# arm-pro-mini.net
KiCad netlist of a schematic drawn in EAGLE
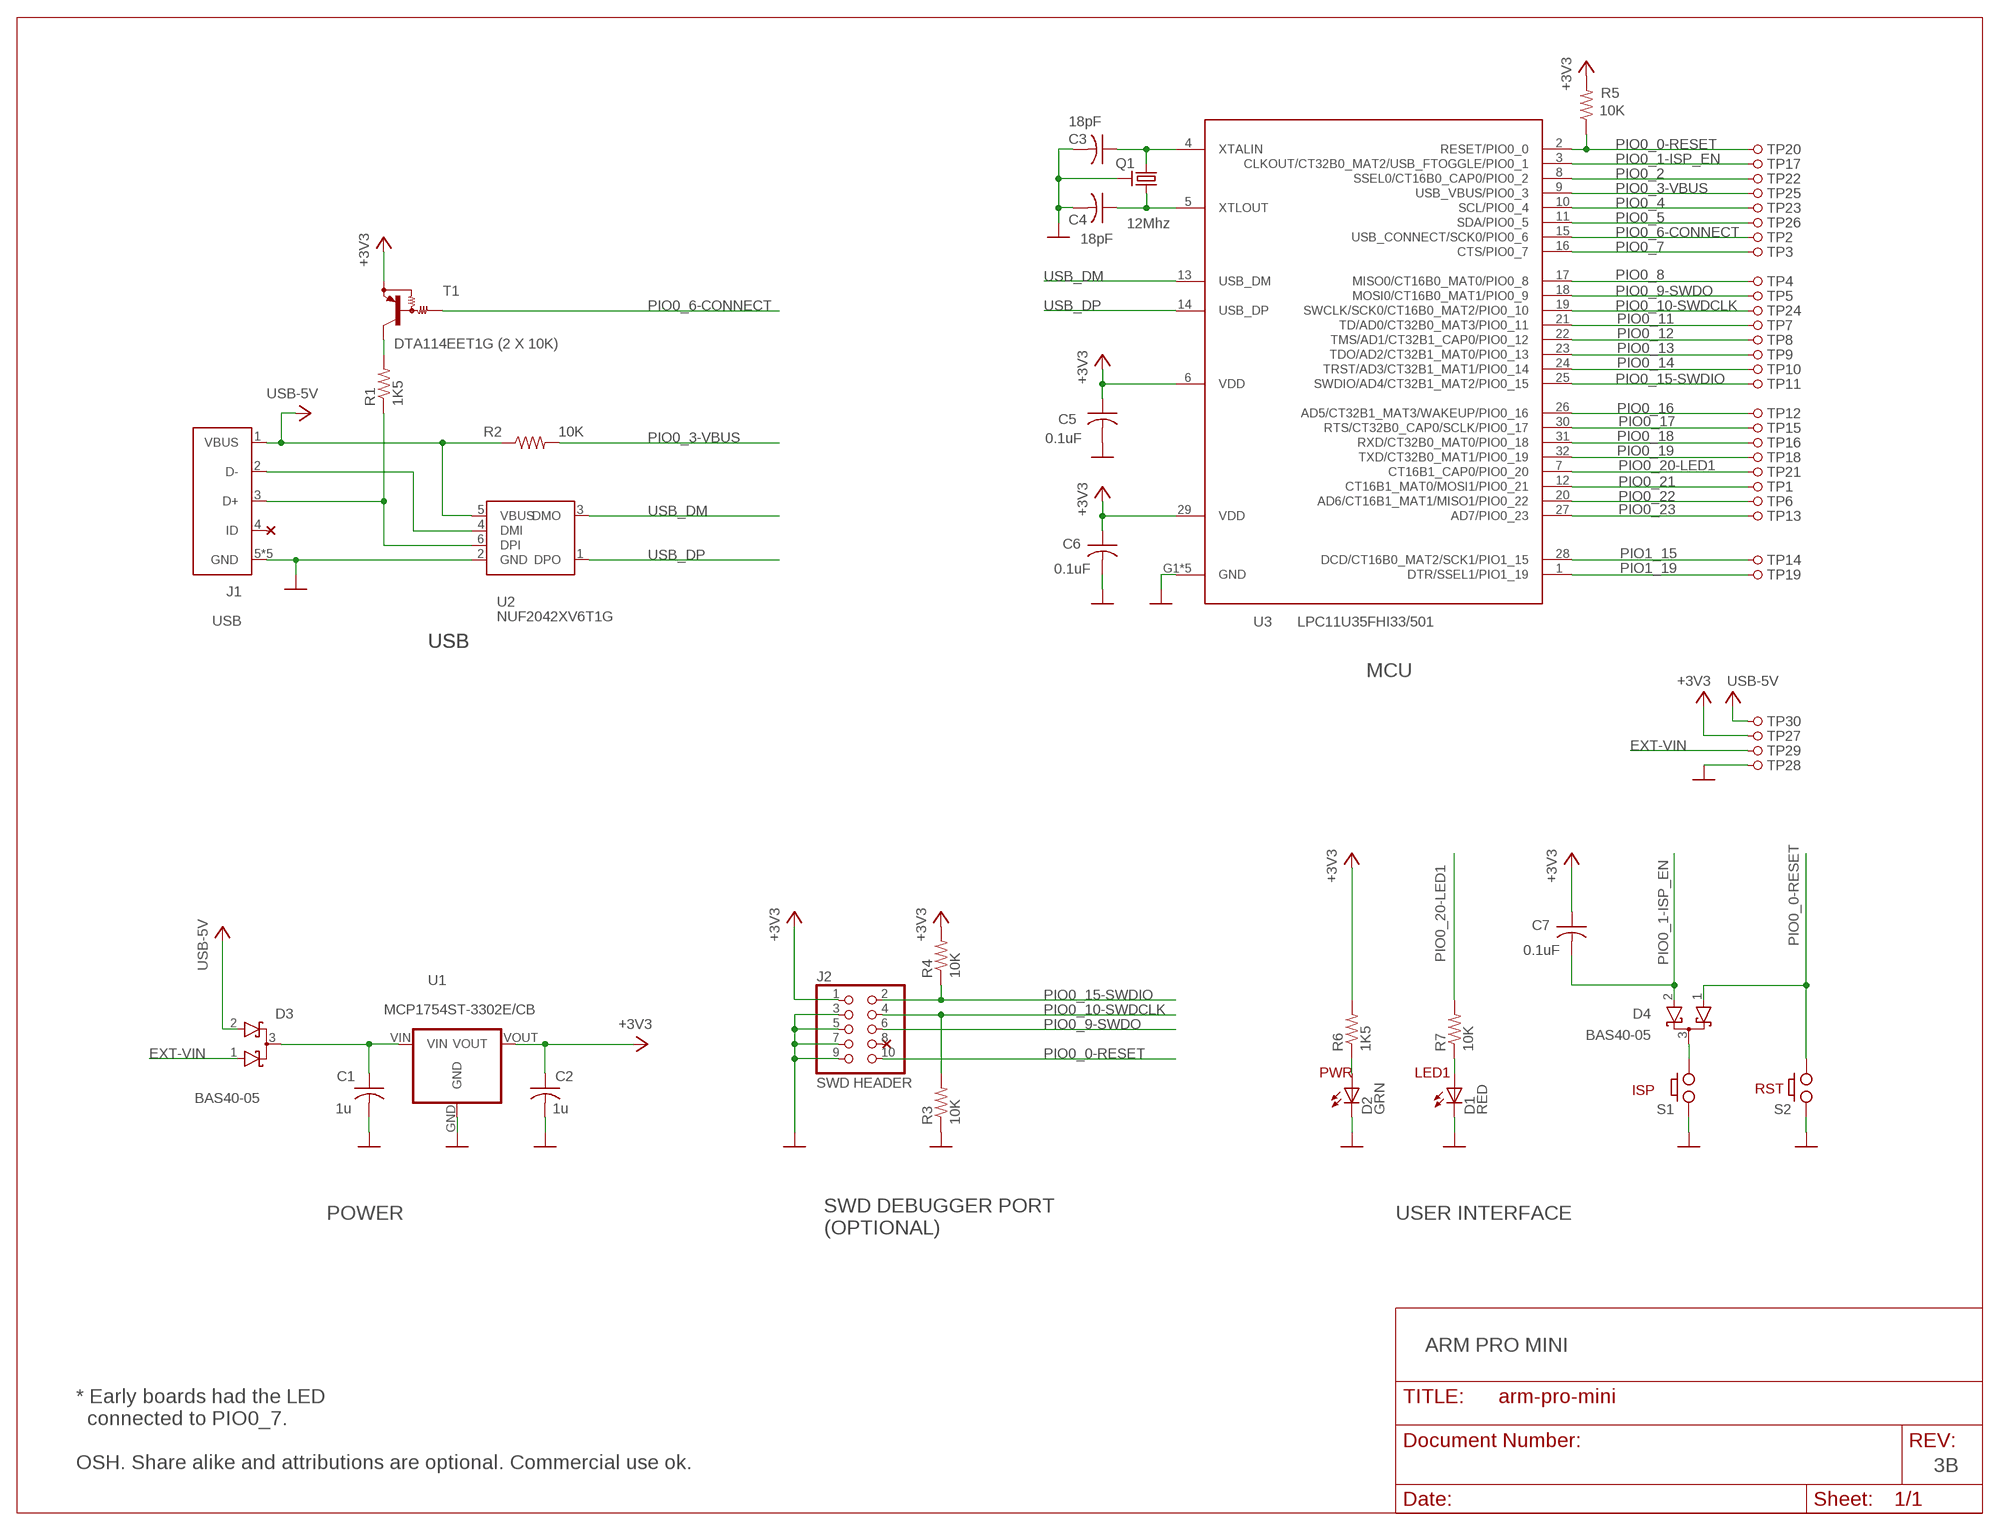
[diagram p0: schematic, sheet 1]

(export (version "E")
  (design (tool "Eeschema 10.0.6"))
  (components
    (comp (ref "C1")
      (value "1u")
      (footprint "eagle-import:C0603K")
      (libsource (lib "eagle-import") (part "CAPACITORC0603K"))
    )
    (comp (ref "C2")
      (value "1u")
      (footprint "eagle-import:C0603K")
      (libsource (lib "eagle-import") (part "CAPACITORC0603K"))
    )
    (comp (ref "C3")
      (value "18pF")
      (footprint "eagle-import:C0402K")
      (libsource (lib "eagle-import") (part "C-USC0402K"))
    )
    (comp (ref "C4")
      (value "18pF")
      (footprint "eagle-import:C0402K")
      (libsource (lib "eagle-import") (part "C-USC0402K"))
    )
    (comp (ref "C5")
      (value "0.1uF")
      (footprint "eagle-import:C0603K")
      (libsource (lib "eagle-import") (part "CAPACITORC0603K"))
    )
    (comp (ref "C6")
      (value "0.1uF")
      (footprint "eagle-import:C0603K")
      (libsource (lib "eagle-import") (part "CAPACITORC0603K"))
    )
    (comp (ref "C7")
      (value "0.1uF")
      (footprint "eagle-import:C0603K")
      (libsource (lib "eagle-import") (part "CAPACITORC0603K"))
    )
    (comp (ref "D1")
      (value "RED")
      (footprint "eagle-import:LED0603")
      (libsource (lib "eagle-import") (part "LED"))
    )
    (comp (ref "D2")
      (value "GRN")
      (footprint "eagle-import:LED0603")
      (libsource (lib "eagle-import") (part "LED"))
    )
    (comp (ref "D3")
      (value "BAS40-05")
      (footprint "eagle-import:SOT23")
      (libsource (lib "eagle-import") (part "BAS40-05"))
    )
    (comp (ref "D4")
      (value "BAS40-05")
      (footprint "eagle-import:SOT23")
      (libsource (lib "eagle-import") (part "BAS40-05"))
    )
    (comp (ref "J1")
      (value "USB")
      (footprint "eagle-import:USB-MICRO")
      (libsource (lib "eagle-import") (part "USB"))
    )
    (comp (ref "J2")
      (value "SWD HEADER")
      (footprint "eagle-import:SWD-HEADER")
      (libsource (lib "eagle-import") (part "SWD-HEADER"))
    )
    (comp (ref "Q1")
      (value "12Mhz")
      (footprint "eagle-import:CRYSTAL")
      (libsource (lib "eagle-import") (part "CRYSTALCTS406"))
    )
    (comp (ref "R1")
      (value "1K5")
      (footprint "eagle-import:R0402")
      (libsource (lib "eagle-import") (part "R-US_R0402"))
    )
    (comp (ref "R2")
      (value "10K")
      (footprint "eagle-import:R0402")
      (libsource (lib "eagle-import") (part "R-US_R0402"))
    )
    (comp (ref "R3")
      (value "10K")
      (footprint "eagle-import:R0402")
      (libsource (lib "eagle-import") (part "R-US_R0402"))
    )
    (comp (ref "R4")
      (value "10K")
      (footprint "eagle-import:R0402")
      (libsource (lib "eagle-import") (part "R-US_R0402"))
    )
    (comp (ref "R5")
      (value "10K")
      (footprint "eagle-import:R0402")
      (libsource (lib "eagle-import") (part "R-US_R0402"))
    )
    (comp (ref "R6")
      (value "1K5")
      (footprint "eagle-import:R0402")
      (libsource (lib "eagle-import") (part "R-US_R0402"))
    )
    (comp (ref "R7")
      (value "10K")
      (footprint "eagle-import:R0402")
      (libsource (lib "eagle-import") (part "R-US_R0402"))
    )
    (comp (ref "S1")
      (value "PUSH_BUTTON")
      (footprint "eagle-import:PUSH_BUTTON")
      (libsource (lib "eagle-import") (part "PUSH_BUTTON"))
    )
    (comp (ref "S2")
      (value "PUSH_BUTTON")
      (footprint "eagle-import:PUSH_BUTTON")
      (libsource (lib "eagle-import") (part "PUSH_BUTTON"))
    )
    (comp (ref "T1")
      (value "DTA114EET1G (2 X 10K)")
      (footprint "eagle-import:SC75-BEC")
      (libsource (lib "eagle-import") (part "PNP_RESISTORS"))
    )
    (comp (ref "TP1")
      (value "HDR1")
      (footprint "eagle-import:1X01")
      (libsource (lib "eagle-import") (part "PINHD-1X1"))
    )
    (comp (ref "TP2")
      (value "HDR1")
      (footprint "eagle-import:1X01")
      (libsource (lib "eagle-import") (part "PINHD-1X1"))
    )
    (comp (ref "TP3")
      (value "HDR1")
      (footprint "eagle-import:1X01")
      (libsource (lib "eagle-import") (part "PINHD-1X1"))
    )
    (comp (ref "TP4")
      (value "HDR1")
      (footprint "eagle-import:1X01")
      (libsource (lib "eagle-import") (part "PINHD-1X1"))
    )
    (comp (ref "TP5")
      (value "HDR1")
      (footprint "eagle-import:1X01")
      (libsource (lib "eagle-import") (part "PINHD-1X1"))
    )
    (comp (ref "TP6")
      (value "HDR1")
      (footprint "eagle-import:1X01")
      (libsource (lib "eagle-import") (part "PINHD-1X1"))
    )
    (comp (ref "TP7")
      (value "HDR1")
      (footprint "eagle-import:1X01")
      (libsource (lib "eagle-import") (part "PINHD-1X1"))
    )
    (comp (ref "TP8")
      (value "HDR1")
      (footprint "eagle-import:1X01")
      (libsource (lib "eagle-import") (part "PINHD-1X1"))
    )
    (comp (ref "TP9")
      (value "HDR1")
      (footprint "eagle-import:1X01")
      (libsource (lib "eagle-import") (part "PINHD-1X1"))
    )
    (comp (ref "TP10")
      (value "HDR1")
      (footprint "eagle-import:1X01")
      (libsource (lib "eagle-import") (part "PINHD-1X1"))
    )
    (comp (ref "TP11")
      (value "HDR1")
      (footprint "eagle-import:1X01")
      (libsource (lib "eagle-import") (part "PINHD-1X1"))
    )
    (comp (ref "TP12")
      (value "HDR1")
      (footprint "eagle-import:1X01")
      (libsource (lib "eagle-import") (part "PINHD-1X1"))
    )
    (comp (ref "TP13")
      (value "HDR1")
      (footprint "eagle-import:1X01")
      (libsource (lib "eagle-import") (part "PINHD-1X1"))
    )
    (comp (ref "TP14")
      (value "HDR1")
      (footprint "eagle-import:1X01")
      (libsource (lib "eagle-import") (part "PINHD-1X1"))
    )
    (comp (ref "TP15")
      (value "HDR1")
      (footprint "eagle-import:1X01")
      (libsource (lib "eagle-import") (part "PINHD-1X1"))
    )
    (comp (ref "TP16")
      (value "HDR1")
      (footprint "eagle-import:1X01")
      (libsource (lib "eagle-import") (part "PINHD-1X1"))
    )
    (comp (ref "TP17")
      (value "HDR1")
      (footprint "eagle-import:1X01")
      (libsource (lib "eagle-import") (part "PINHD-1X1"))
    )
    (comp (ref "TP18")
      (value "HDR1")
      (footprint "eagle-import:1X01")
      (libsource (lib "eagle-import") (part "PINHD-1X1"))
    )
    (comp (ref "TP19")
      (value "HDR1")
      (footprint "eagle-import:1X01")
      (libsource (lib "eagle-import") (part "PINHD-1X1"))
    )
    (comp (ref "TP20")
      (value "HDR1")
      (footprint "eagle-import:1X01")
      (libsource (lib "eagle-import") (part "PINHD-1X1"))
    )
    (comp (ref "TP21")
      (value "HDR1")
      (footprint "eagle-import:1X01")
      (libsource (lib "eagle-import") (part "PINHD-1X1"))
    )
    (comp (ref "TP22")
      (value "HDR1")
      (footprint "eagle-import:1X01")
      (libsource (lib "eagle-import") (part "PINHD-1X1"))
    )
    (comp (ref "TP23")
      (value "HDR1")
      (footprint "eagle-import:1X01")
      (libsource (lib "eagle-import") (part "PINHD-1X1"))
    )
    (comp (ref "TP24")
      (value "HDR1")
      (footprint "eagle-import:1X01")
      (libsource (lib "eagle-import") (part "PINHD-1X1"))
    )
    (comp (ref "TP25")
      (value "HDR1")
      (footprint "eagle-import:1X01")
      (libsource (lib "eagle-import") (part "PINHD-1X1"))
    )
    (comp (ref "TP26")
      (value "HDR1")
      (footprint "eagle-import:1X01")
      (libsource (lib "eagle-import") (part "PINHD-1X1"))
    )
    (comp (ref "TP27")
      (value "HDR1")
      (footprint "eagle-import:1X01")
      (libsource (lib "eagle-import") (part "PINHD-1X1"))
    )
    (comp (ref "TP28")
      (value "HDR1")
      (footprint "eagle-import:1X01")
      (libsource (lib "eagle-import") (part "PINHD-1X1"))
    )
    (comp (ref "TP29")
      (value "HDR1")
      (footprint "eagle-import:1X01")
      (libsource (lib "eagle-import") (part "PINHD-1X1"))
    )
    (comp (ref "TP30")
      (value "HDR1")
      (footprint "eagle-import:1X01")
      (libsource (lib "eagle-import") (part "PINHD-1X1"))
    )
    (comp (ref "U1")
      (value "MCP1754ST-3302E/CB")
      (footprint "eagle-import:SOT-23A")
      (libsource (lib "eagle-import") (part "LDO"))
    )
    (comp (ref "U2")
      (value "NUF2042XV6T1G")
      (footprint "eagle-import:SOT-563")
      (libsource (lib "eagle-import") (part "USB_FILTER"))
    )
    (comp (ref "U3")
      (value "LPC11U35FHI33/501")
      (footprint "eagle-import:HVQFN33-5MM")
      (libsource (lib "eagle-import") (part "LPC11U35FHN33/501"))
    )
  )
  (nets
    (net (code "1") (name "+3V3") (class "Default")
      (node (ref "C2") (pin "1") (pinfunction "1_1") (pintype "passive"))
      (node (ref "C5") (pin "1") (pinfunction "1_1") (pintype "passive"))
      (node (ref "C6") (pin "1") (pinfunction "1_1") (pintype "passive"))
      (node (ref "C7") (pin "1") (pinfunction "1_1") (pintype "passive"))
      (node (ref "J2") (pin "1") (pinfunction "1_1") (pintype "passive"))
      (node (ref "R4") (pin "2") (pinfunction "2_2") (pintype "passive"))
      (node (ref "R5") (pin "2") (pinfunction "2_2") (pintype "passive"))
      (node (ref "R6") (pin "2") (pinfunction "2_2") (pintype "passive"))
      (node (ref "T1") (pin "E") (pinfunction "E_E") (pintype "passive"))
      (node (ref "TP27") (pin "1") (pinfunction "1_1") (pintype "passive"))
      (node (ref "U1") (pin "VOUT") (pinfunction "VOUT_VOUT") (pintype "power_in"))
      (node (ref "U3") (pin "29") (pinfunction "VDD_29") (pintype "bidirectional"))
      (node (ref "U3") (pin "6") (pinfunction "VDD_6") (pintype "bidirectional"))
    )
    (net (code "2") (name "/EXT-VIN") (class "Default")
      (node (ref "D3") (pin "1") (pinfunction "A1_1") (pintype "passive"))
      (node (ref "TP29") (pin "1") (pinfunction "1_1") (pintype "passive"))
    )
    (net (code "3") (name "/PIO0_0-RESET") (class "Default")
      (node (ref "D4") (pin "1") (pinfunction "A1_1") (pintype "passive"))
      (node (ref "J2") (pin "10") (pinfunction "10_10") (pintype "passive"))
      (node (ref "R5") (pin "1") (pinfunction "1_1") (pintype "passive"))
      (node (ref "S2") (pin "B2") (pinfunction "2_B2") (pintype "passive"))
      (node (ref "S2") (pin "B2P") (pinfunction "2_B2P") (pintype "passive"))
      (node (ref "TP20") (pin "1") (pinfunction "1_1") (pintype "passive"))
      (node (ref "U3") (pin "2") (pinfunction "RESET/PIO0_0_2") (pintype "bidirectional"))
    )
    (net (code "4") (name "/PIO0_1-ISP_EN") (class "Default")
      (node (ref "C7") (pin "2") (pinfunction "2_2") (pintype "passive"))
      (node (ref "D4") (pin "2") (pinfunction "A2_2") (pintype "passive"))
      (node (ref "TP17") (pin "1") (pinfunction "1_1") (pintype "passive"))
      (node (ref "U3") (pin "3") (pinfunction "CLKOUT/CT32B0_MAT2/USB_FTOGGLE/PIO0_1_3") (pintype "bidirectional"))
    )
    (net (code "5") (name "/PIO0_2") (class "Default")
      (node (ref "TP22") (pin "1") (pinfunction "1_1") (pintype "passive"))
      (node (ref "U3") (pin "8") (pinfunction "SSEL0/CT16B0_CAP0/PIO0_2_8") (pintype "bidirectional"))
    )
    (net (code "6") (name "/PIO0_3-VBUS") (class "Default")
      (node (ref "R2") (pin "2") (pinfunction "2_2") (pintype "passive"))
      (node (ref "TP25") (pin "1") (pinfunction "1_1") (pintype "passive"))
      (node (ref "U3") (pin "9") (pinfunction "USB_VBUS/PIO0_3_9") (pintype "bidirectional"))
    )
    (net (code "7") (name "/PIO0_4") (class "Default")
      (node (ref "TP23") (pin "1") (pinfunction "1_1") (pintype "passive"))
      (node (ref "U3") (pin "10") (pinfunction "SCL/PIO0_4_10") (pintype "bidirectional"))
    )
    (net (code "8") (name "/PIO0_5") (class "Default")
      (node (ref "TP26") (pin "1") (pinfunction "1_1") (pintype "passive"))
      (node (ref "U3") (pin "11") (pinfunction "SDA/PIO0_5_11") (pintype "bidirectional"))
    )
    (net (code "9") (name "/PIO0_6-CONNECT") (class "Default")
      (node (ref "T1") (pin "B") (pinfunction "B_B") (pintype "passive"))
      (node (ref "TP2") (pin "1") (pinfunction "1_1") (pintype "passive"))
      (node (ref "U3") (pin "15") (pinfunction "USB_CONNECT/SCK0/PIO0_6_15") (pintype "bidirectional"))
    )
    (net (code "10") (name "/PIO0_7") (class "Default")
      (node (ref "TP3") (pin "1") (pinfunction "1_1") (pintype "passive"))
      (node (ref "U3") (pin "16") (pinfunction "CTS/PIO0_7_16") (pintype "bidirectional"))
    )
    (net (code "11") (name "/PIO0_8") (class "Default")
      (node (ref "TP4") (pin "1") (pinfunction "1_1") (pintype "passive"))
      (node (ref "U3") (pin "17") (pinfunction "MISO0/CT16B0_MAT0/PIO0_8_17") (pintype "bidirectional"))
    )
    (net (code "12") (name "/PIO0_9-SWDO") (class "Default")
      (node (ref "J2") (pin "6") (pinfunction "6_6") (pintype "passive"))
      (node (ref "TP5") (pin "1") (pinfunction "1_1") (pintype "passive"))
      (node (ref "U3") (pin "18") (pinfunction "MOSI0/CT16B0_MAT1/PIO0_9_18") (pintype "bidirectional"))
    )
    (net (code "13") (name "/PIO0_10-SWDCLK") (class "Default")
      (node (ref "J2") (pin "4") (pinfunction "4_4") (pintype "passive"))
      (node (ref "R3") (pin "2") (pinfunction "2_2") (pintype "passive"))
      (node (ref "TP24") (pin "1") (pinfunction "1_1") (pintype "passive"))
      (node (ref "U3") (pin "19") (pinfunction "SWCLK/SCK0/CT16B0_MAT2/PIO0_10_19") (pintype "bidirectional"))
    )
    (net (code "14") (name "/PIO0_11") (class "Default")
      (node (ref "TP7") (pin "1") (pinfunction "1_1") (pintype "passive"))
      (node (ref "U3") (pin "21") (pinfunction "TD/AD0/CT32B0_MAT3/PIO0_11_21") (pintype "bidirectional"))
    )
    (net (code "15") (name "/PIO0_12") (class "Default")
      (node (ref "TP8") (pin "1") (pinfunction "1_1") (pintype "passive"))
      (node (ref "U3") (pin "22") (pinfunction "TMS/AD1/CT32B1_CAP0/PIO0_12_22") (pintype "bidirectional"))
    )
    (net (code "16") (name "/PIO0_13") (class "Default")
      (node (ref "TP9") (pin "1") (pinfunction "1_1") (pintype "passive"))
      (node (ref "U3") (pin "23") (pinfunction "TDO/AD2/CT32B1_MAT0/PIO0_13_23") (pintype "bidirectional"))
    )
    (net (code "17") (name "/PIO0_14") (class "Default")
      (node (ref "TP10") (pin "1") (pinfunction "1_1") (pintype "passive"))
      (node (ref "U3") (pin "24") (pinfunction "TRST/AD3/CT32B1_MAT1/PIO0_14_24") (pintype "bidirectional"))
    )
    (net (code "18") (name "/PIO0_15-SWDIO") (class "Default")
      (node (ref "J2") (pin "2") (pinfunction "2_2") (pintype "passive"))
      (node (ref "R4") (pin "1") (pinfunction "1_1") (pintype "passive"))
      (node (ref "TP11") (pin "1") (pinfunction "1_1") (pintype "passive"))
      (node (ref "U3") (pin "25") (pinfunction "SWDIO/AD4/CT32B1_MAT2/PIO0_15_25") (pintype "bidirectional"))
    )
    (net (code "19") (name "/PIO0_16") (class "Default")
      (node (ref "TP12") (pin "1") (pinfunction "1_1") (pintype "passive"))
      (node (ref "U3") (pin "26") (pinfunction "AD5/CT32B1_MAT3/WAKEUP/PIO0_16_26") (pintype "bidirectional"))
    )
    (net (code "20") (name "/PIO0_17") (class "Default")
      (node (ref "TP15") (pin "1") (pinfunction "1_1") (pintype "passive"))
      (node (ref "U3") (pin "30") (pinfunction "RTS/CT32B0_CAP0/SCLK/PIO0_17_30") (pintype "bidirectional"))
    )
    (net (code "21") (name "/PIO0_18") (class "Default")
      (node (ref "TP16") (pin "1") (pinfunction "1_1") (pintype "passive"))
      (node (ref "U3") (pin "31") (pinfunction "RXD/CT32B0_MAT0/PIO0_18_31") (pintype "bidirectional"))
    )
    (net (code "22") (name "/PIO0_19") (class "Default")
      (node (ref "TP18") (pin "1") (pinfunction "1_1") (pintype "passive"))
      (node (ref "U3") (pin "32") (pinfunction "TXD/CT32B0_MAT1/PIO0_19_32") (pintype "bidirectional"))
    )
    (net (code "23") (name "/PIO0_20-LED1") (class "Default")
      (node (ref "R7") (pin "2") (pinfunction "2_2") (pintype "passive"))
      (node (ref "TP21") (pin "1") (pinfunction "1_1") (pintype "passive"))
      (node (ref "U3") (pin "7") (pinfunction "CT16B1_CAP0/PIO0_20_7") (pintype "bidirectional"))
    )
    (net (code "24") (name "/PIO0_21") (class "Default")
      (node (ref "TP1") (pin "1") (pinfunction "1_1") (pintype "passive"))
      (node (ref "U3") (pin "12") (pinfunction "CT16B1_MAT0/MOSI1/PIO0_21_12") (pintype "bidirectional"))
    )
    (net (code "25") (name "/PIO0_22") (class "Default")
      (node (ref "TP6") (pin "1") (pinfunction "1_1") (pintype "passive"))
      (node (ref "U3") (pin "20") (pinfunction "AD6/CT16B1_MAT1/MISO1/PIO0_22_20") (pintype "bidirectional"))
    )
    (net (code "26") (name "/PIO0_23") (class "Default")
      (node (ref "TP13") (pin "1") (pinfunction "1_1") (pintype "passive"))
      (node (ref "U3") (pin "27") (pinfunction "AD7/PIO0_23_27") (pintype "bidirectional"))
    )
    (net (code "27") (name "/PIO1_15") (class "Default")
      (node (ref "TP14") (pin "1") (pinfunction "1_1") (pintype "passive"))
      (node (ref "U3") (pin "28") (pinfunction "DCD/CT16B0_MAT2/SCK1/PIO1_15_28") (pintype "bidirectional"))
    )
    (net (code "28") (name "/PIO1_19") (class "Default")
      (node (ref "TP19") (pin "1") (pinfunction "1_1") (pintype "passive"))
      (node (ref "U3") (pin "1") (pinfunction "DTR/SSEL1/PIO1_19_1") (pintype "bidirectional"))
    )
    (net (code "29") (name "/USB_DM") (class "Default")
      (node (ref "U2") (pin "3") (pinfunction "DMO_3") (pintype "passive"))
      (node (ref "U3") (pin "13") (pinfunction "USB_DM_13") (pintype "bidirectional"))
    )
    (net (code "30") (name "/USB_DP") (class "Default")
      (node (ref "U2") (pin "1") (pinfunction "DPO_1") (pintype "passive"))
      (node (ref "U3") (pin "14") (pinfunction "USB_DP_14") (pintype "bidirectional"))
    )
    (net (code "31") (name "GND") (class "Default")
      (node (ref "C1") (pin "2") (pinfunction "2_2") (pintype "passive"))
      (node (ref "C2") (pin "2") (pinfunction "2_2") (pintype "passive"))
      (node (ref "C3") (pin "2") (pinfunction "2_2") (pintype "passive"))
      (node (ref "C4") (pin "2") (pinfunction "2_2") (pintype "passive"))
      (node (ref "C5") (pin "2") (pinfunction "2_2") (pintype "passive"))
      (node (ref "C6") (pin "2") (pinfunction "2_2") (pintype "passive"))
      (node (ref "D1") (pin "C") (pinfunction "C_C") (pintype "passive"))
      (node (ref "D2") (pin "C") (pinfunction "C_C") (pintype "passive"))
      (node (ref "J1") (pin "5") (pinfunction "GND_5") (pintype "bidirectional"))
      (node (ref "J1") (pin "G1") (pinfunction "GND_G1") (pintype "bidirectional"))
      (node (ref "J1") (pin "G2") (pinfunction "GND_G2") (pintype "bidirectional"))
      (node (ref "J1") (pin "G3") (pinfunction "GND_G3") (pintype "bidirectional"))
      (node (ref "J1") (pin "G4") (pinfunction "GND_G4") (pintype "bidirectional"))
      (node (ref "J2") (pin "3") (pinfunction "3_3") (pintype "passive"))
      (node (ref "J2") (pin "5") (pinfunction "5_5") (pintype "passive"))
      (node (ref "J2") (pin "7") (pinfunction "7_7") (pintype "passive"))
      (node (ref "J2") (pin "9") (pinfunction "9_9") (pintype "passive"))
      (node (ref "Q1") (pin "2") (pinfunction "GND_2") (pintype "power_in"))
      (node (ref "Q1") (pin "4") (pinfunction "GND_4") (pintype "power_in"))
      (node (ref "R3") (pin "1") (pinfunction "1_1") (pintype "passive"))
      (node (ref "S1") (pin "A1") (pinfunction "1_A1") (pintype "passive"))
      (node (ref "S1") (pin "A1P") (pinfunction "1_A1P") (pintype "passive"))
      (node (ref "S2") (pin "A1") (pinfunction "1_A1") (pintype "passive"))
      (node (ref "S2") (pin "A1P") (pinfunction "1_A1P") (pintype "passive"))
      (node (ref "TP28") (pin "1") (pinfunction "1_1") (pintype "passive"))
      (node (ref "U1") (pin "GND") (pinfunction "GND_GND") (pintype "power_in"))
      (node (ref "U2") (pin "2") (pinfunction "GND_2") (pintype "power_in"))
      (node (ref "U3") (pin "G1") (pinfunction "GND_G1") (pintype "bidirectional"))
      (node (ref "U3") (pin "G2") (pinfunction "GND_G2") (pintype "bidirectional"))
      (node (ref "U3") (pin "G3") (pinfunction "GND_G3") (pintype "bidirectional"))
      (node (ref "U3") (pin "G4") (pinfunction "GND_G4") (pintype "bidirectional"))
      (node (ref "U3") (pin "TAB") (pinfunction "GND_TAB") (pintype "bidirectional"))
    )
    (net (code "32") (name "Net-(D1-PadA)") (class "Default")
      (node (ref "D1") (pin "A") (pinfunction "A_A") (pintype "passive"))
      (node (ref "R7") (pin "1") (pinfunction "1_1") (pintype "passive"))
    )
    (net (code "33") (name "Net-(D2-PadA)") (class "Default")
      (node (ref "D2") (pin "A") (pinfunction "A_A") (pintype "passive"))
      (node (ref "R6") (pin "1") (pinfunction "1_1") (pintype "passive"))
    )
    (net (code "34") (name "Net-(D3-C)") (class "Default")
      (node (ref "C1") (pin "1") (pinfunction "1_1") (pintype "passive"))
      (node (ref "D3") (pin "3") (pinfunction "C_3") (pintype "passive"))
      (node (ref "U1") (pin "VIN") (pinfunction "VIN_VIN") (pintype "power_in"))
    )
    (net (code "35") (name "Net-(D4-C)") (class "Default")
      (node (ref "D4") (pin "3") (pinfunction "C_3") (pintype "passive"))
      (node (ref "S1") (pin "B2") (pinfunction "2_B2") (pintype "passive"))
      (node (ref "S1") (pin "B2P") (pinfunction "2_B2P") (pintype "passive"))
    )
    (net (code "36") (name "Net-(J1-D+)") (class "Default")
      (node (ref "J1") (pin "3") (pinfunction "D+_3") (pintype "bidirectional"))
      (node (ref "R1") (pin "1") (pinfunction "1_1") (pintype "passive"))
      (node (ref "U2") (pin "6") (pinfunction "DPI_6") (pintype "passive"))
    )
    (net (code "37") (name "Net-(J1-D-)") (class "Default")
      (node (ref "J1") (pin "2") (pinfunction "D-_2") (pintype "bidirectional"))
      (node (ref "U2") (pin "4") (pinfunction "DMI_4") (pintype "passive"))
    )
    (net (code "38") (name "Net-(Q1-2)") (class "Default")
      (node (ref "C3") (pin "1") (pinfunction "1_1") (pintype "passive"))
      (node (ref "Q1") (pin "3") (pinfunction "2_3") (pintype "passive"))
      (node (ref "U3") (pin "4") (pinfunction "XTALIN_4") (pintype "bidirectional"))
    )
    (net (code "39") (name "Net-(R1-Pad2)") (class "Default")
      (node (ref "R1") (pin "2") (pinfunction "2_2") (pintype "passive"))
      (node (ref "T1") (pin "C") (pinfunction "C_C") (pintype "passive"))
    )
    (net (code "40") (name "Net-(U3-XTLOUT)") (class "Default")
      (node (ref "C4") (pin "1") (pinfunction "1_1") (pintype "passive"))
      (node (ref "Q1") (pin "1") (pinfunction "1_1") (pintype "passive"))
      (node (ref "U3") (pin "5") (pinfunction "XTLOUT_5") (pintype "bidirectional"))
    )
    (net (code "41") (name "USB-5V") (class "Default")
      (node (ref "D3") (pin "2") (pinfunction "A2_2") (pintype "passive"))
      (node (ref "J1") (pin "1") (pinfunction "VBUS_1") (pintype "bidirectional"))
      (node (ref "R2") (pin "1") (pinfunction "1_1") (pintype "passive"))
      (node (ref "TP30") (pin "1") (pinfunction "1_1") (pintype "passive"))
      (node (ref "U2") (pin "5") (pinfunction "VBUS_5") (pintype "power_in"))
    )
    (net (code "42") (name "unconnected-(J1-ID-Pad4)") (class "Default")
      (node (ref "J1") (pin "4") (pinfunction "ID_4") (pintype "bidirectional"))
    )
    (net (code "43") (name "unconnected-(J2-Pad8)") (class "Default")
      (node (ref "J2") (pin "8") (pinfunction "8_8") (pintype "passive"))
    )
  )
)
